# oresat0-plusz-end-card.net
KiCad netlist of a schematic drawn in EAGLE
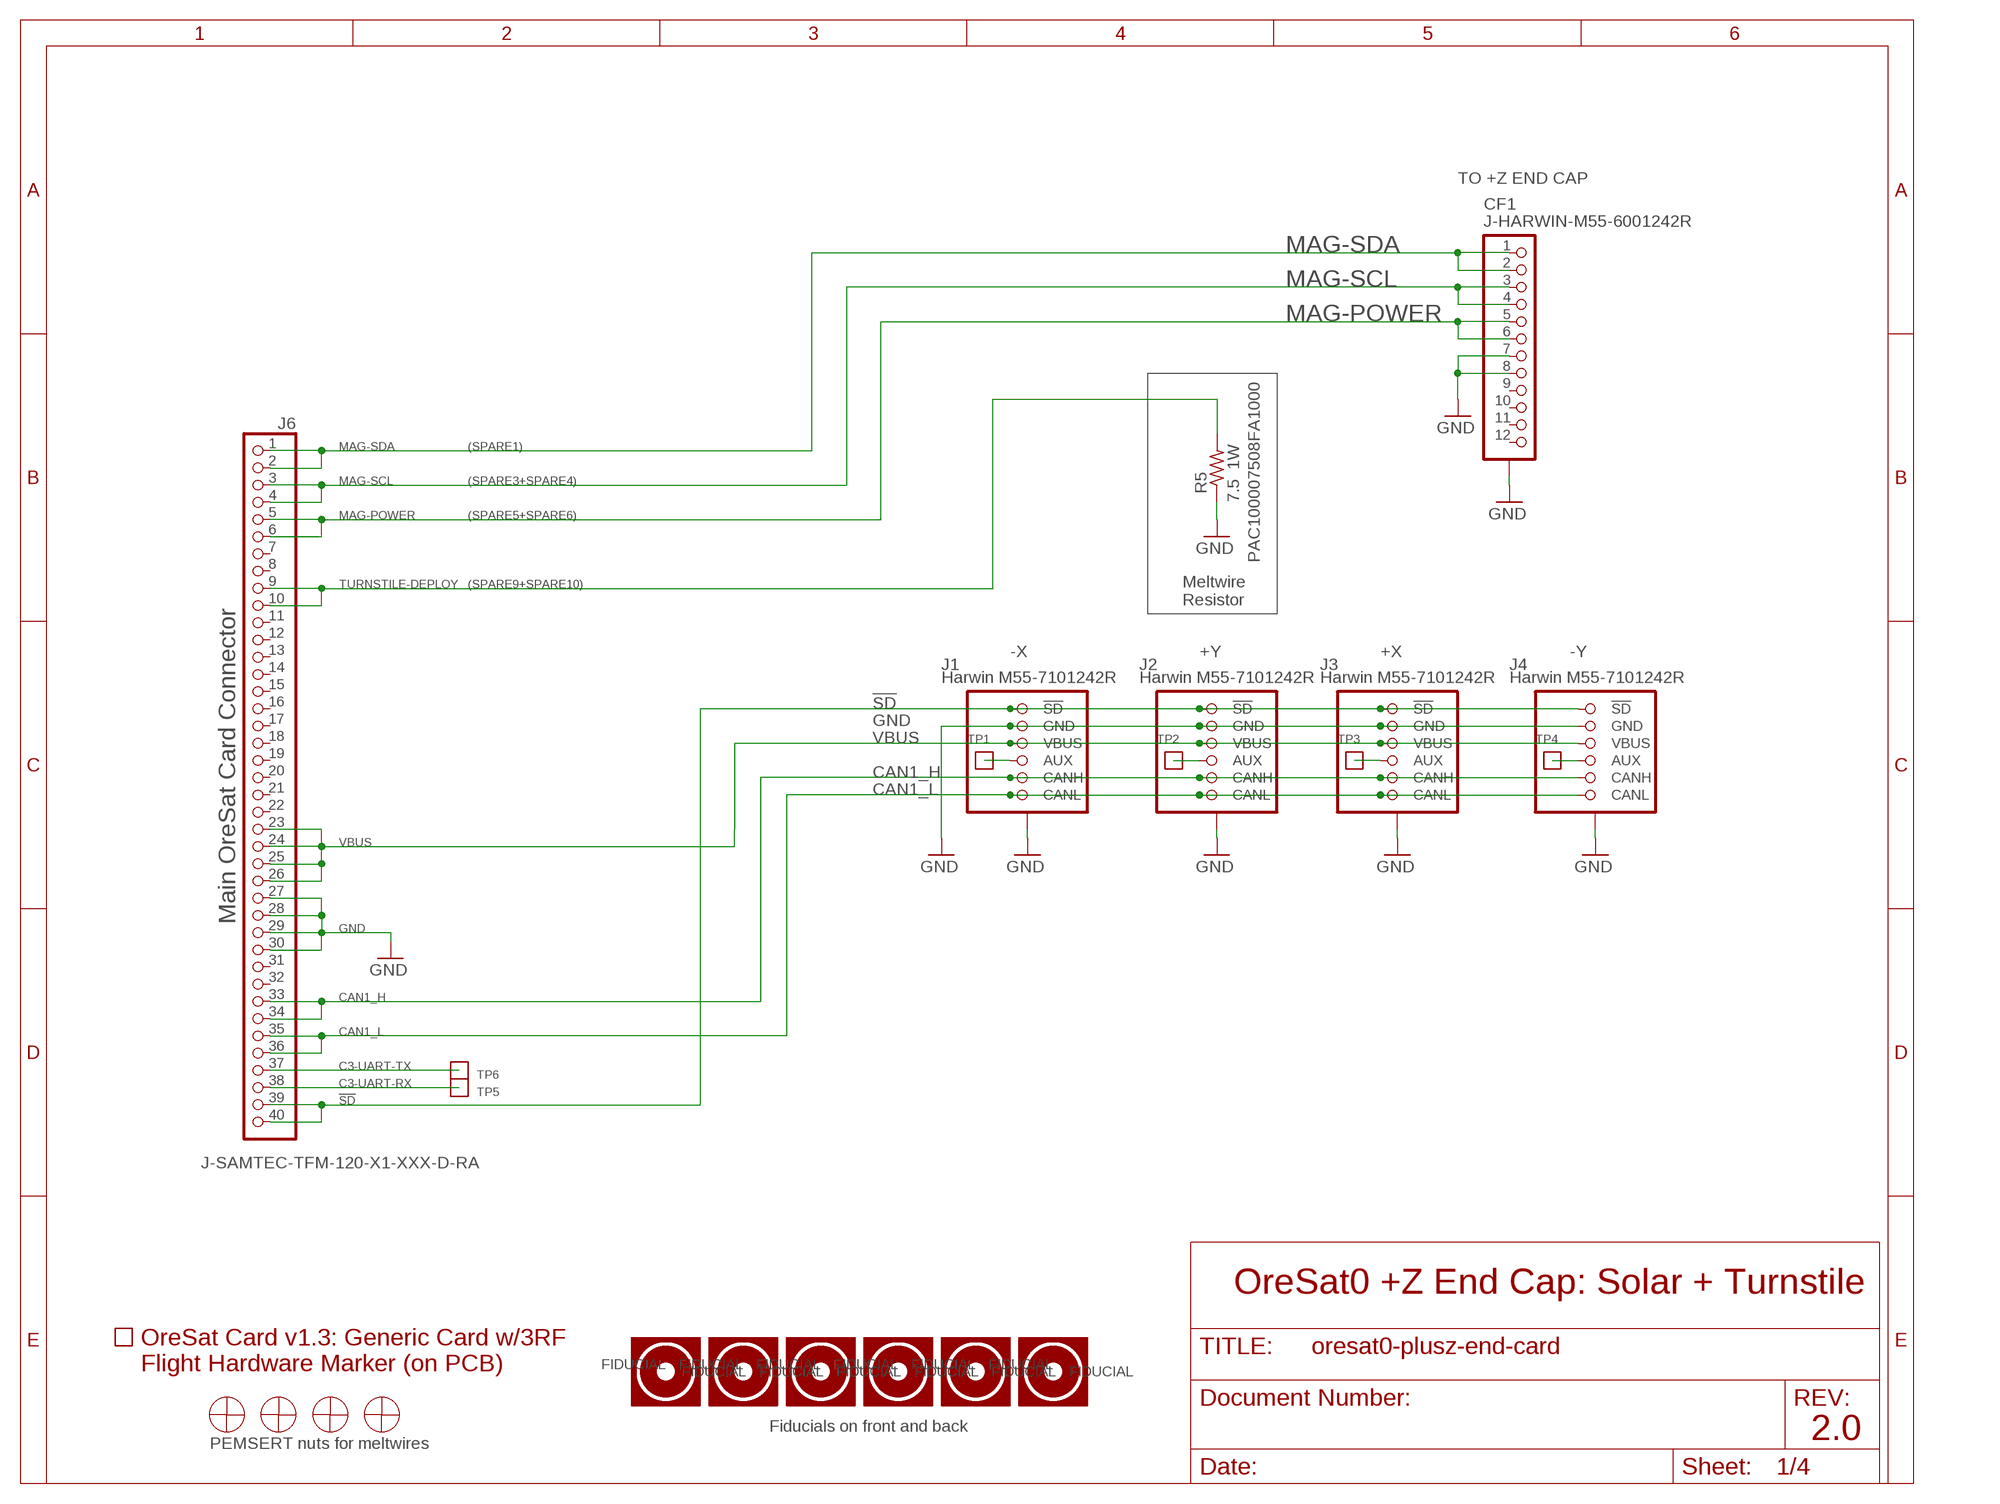
[diagram p0: schematic, sheet 1]
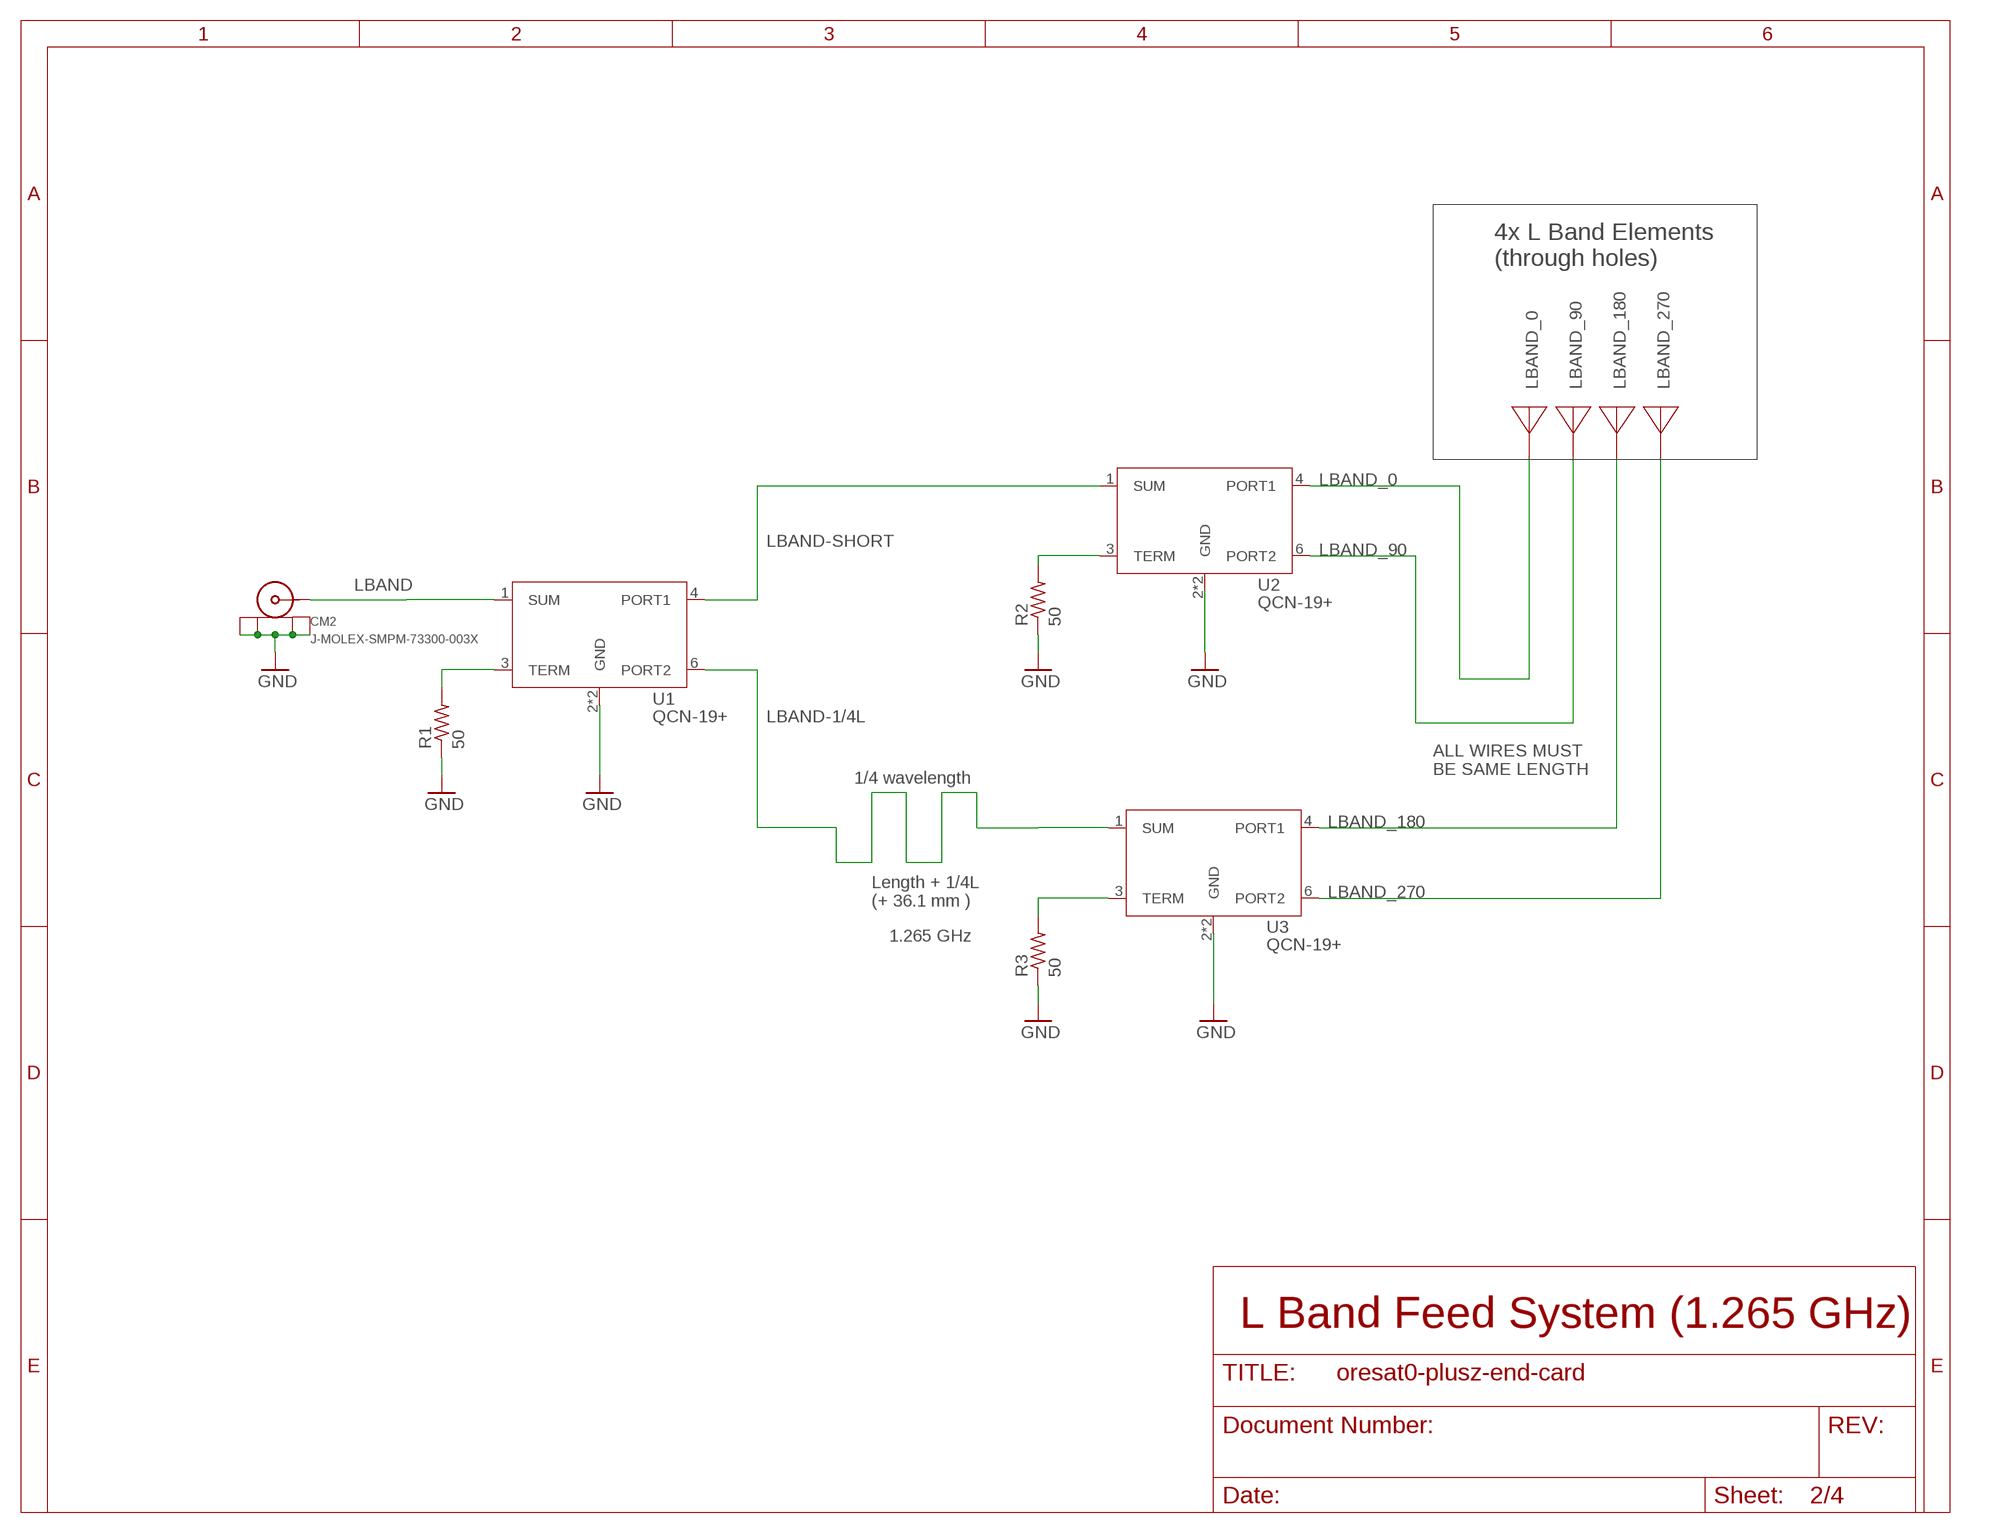
[diagram p1: schematic, sheet 2]
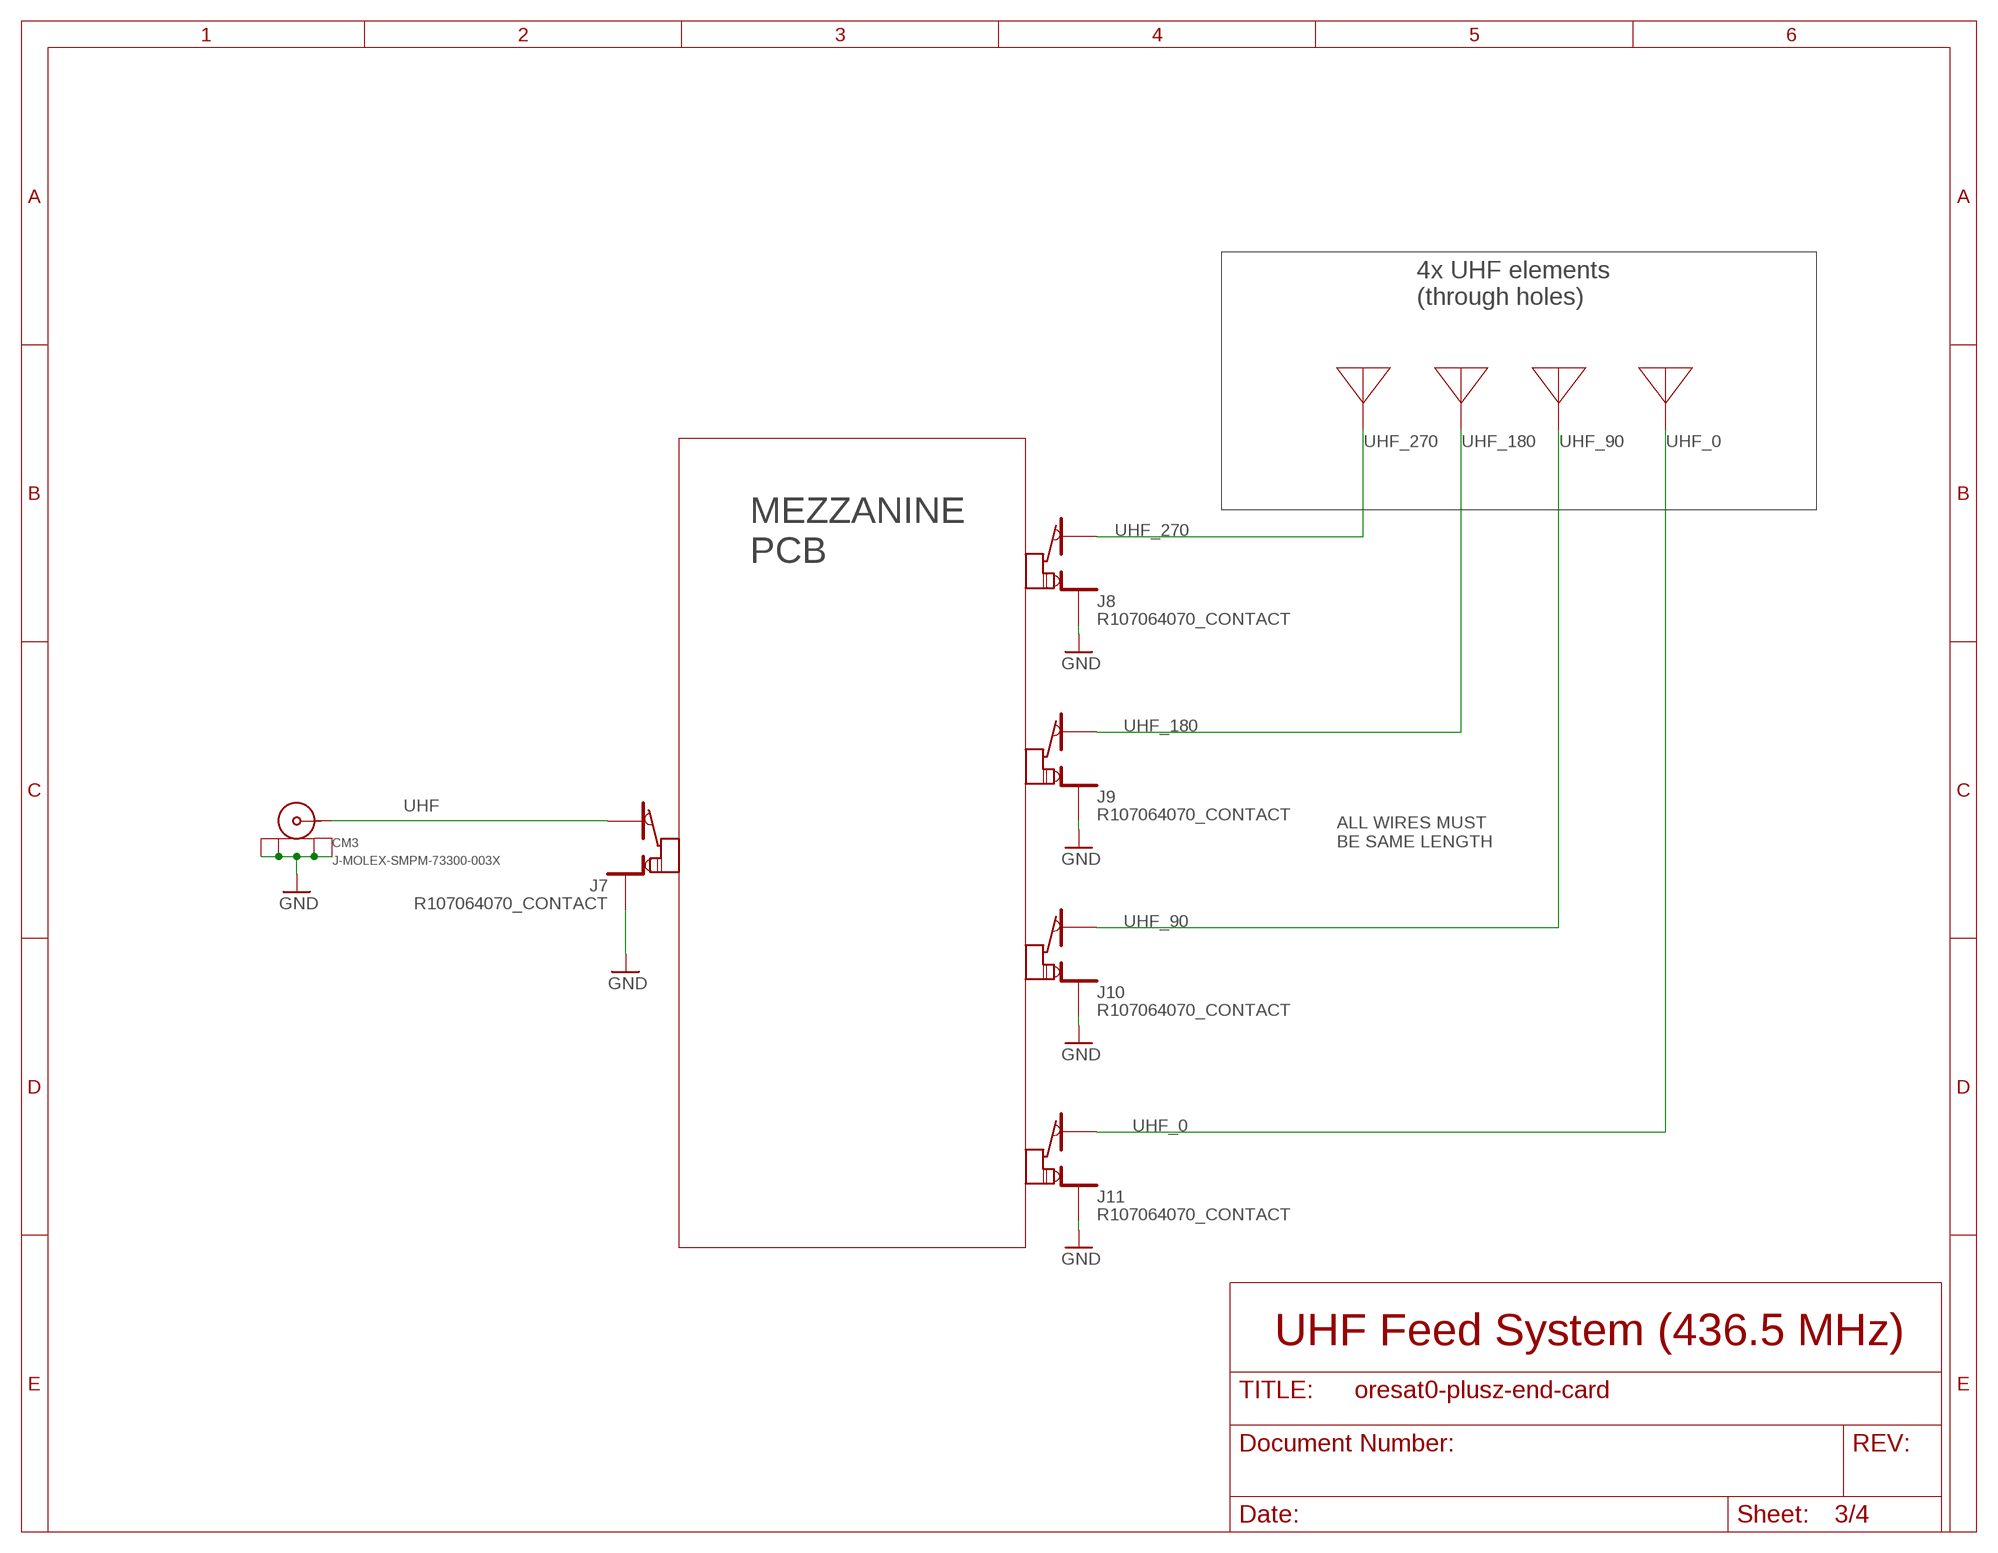
[diagram p2: schematic, sheet 3]
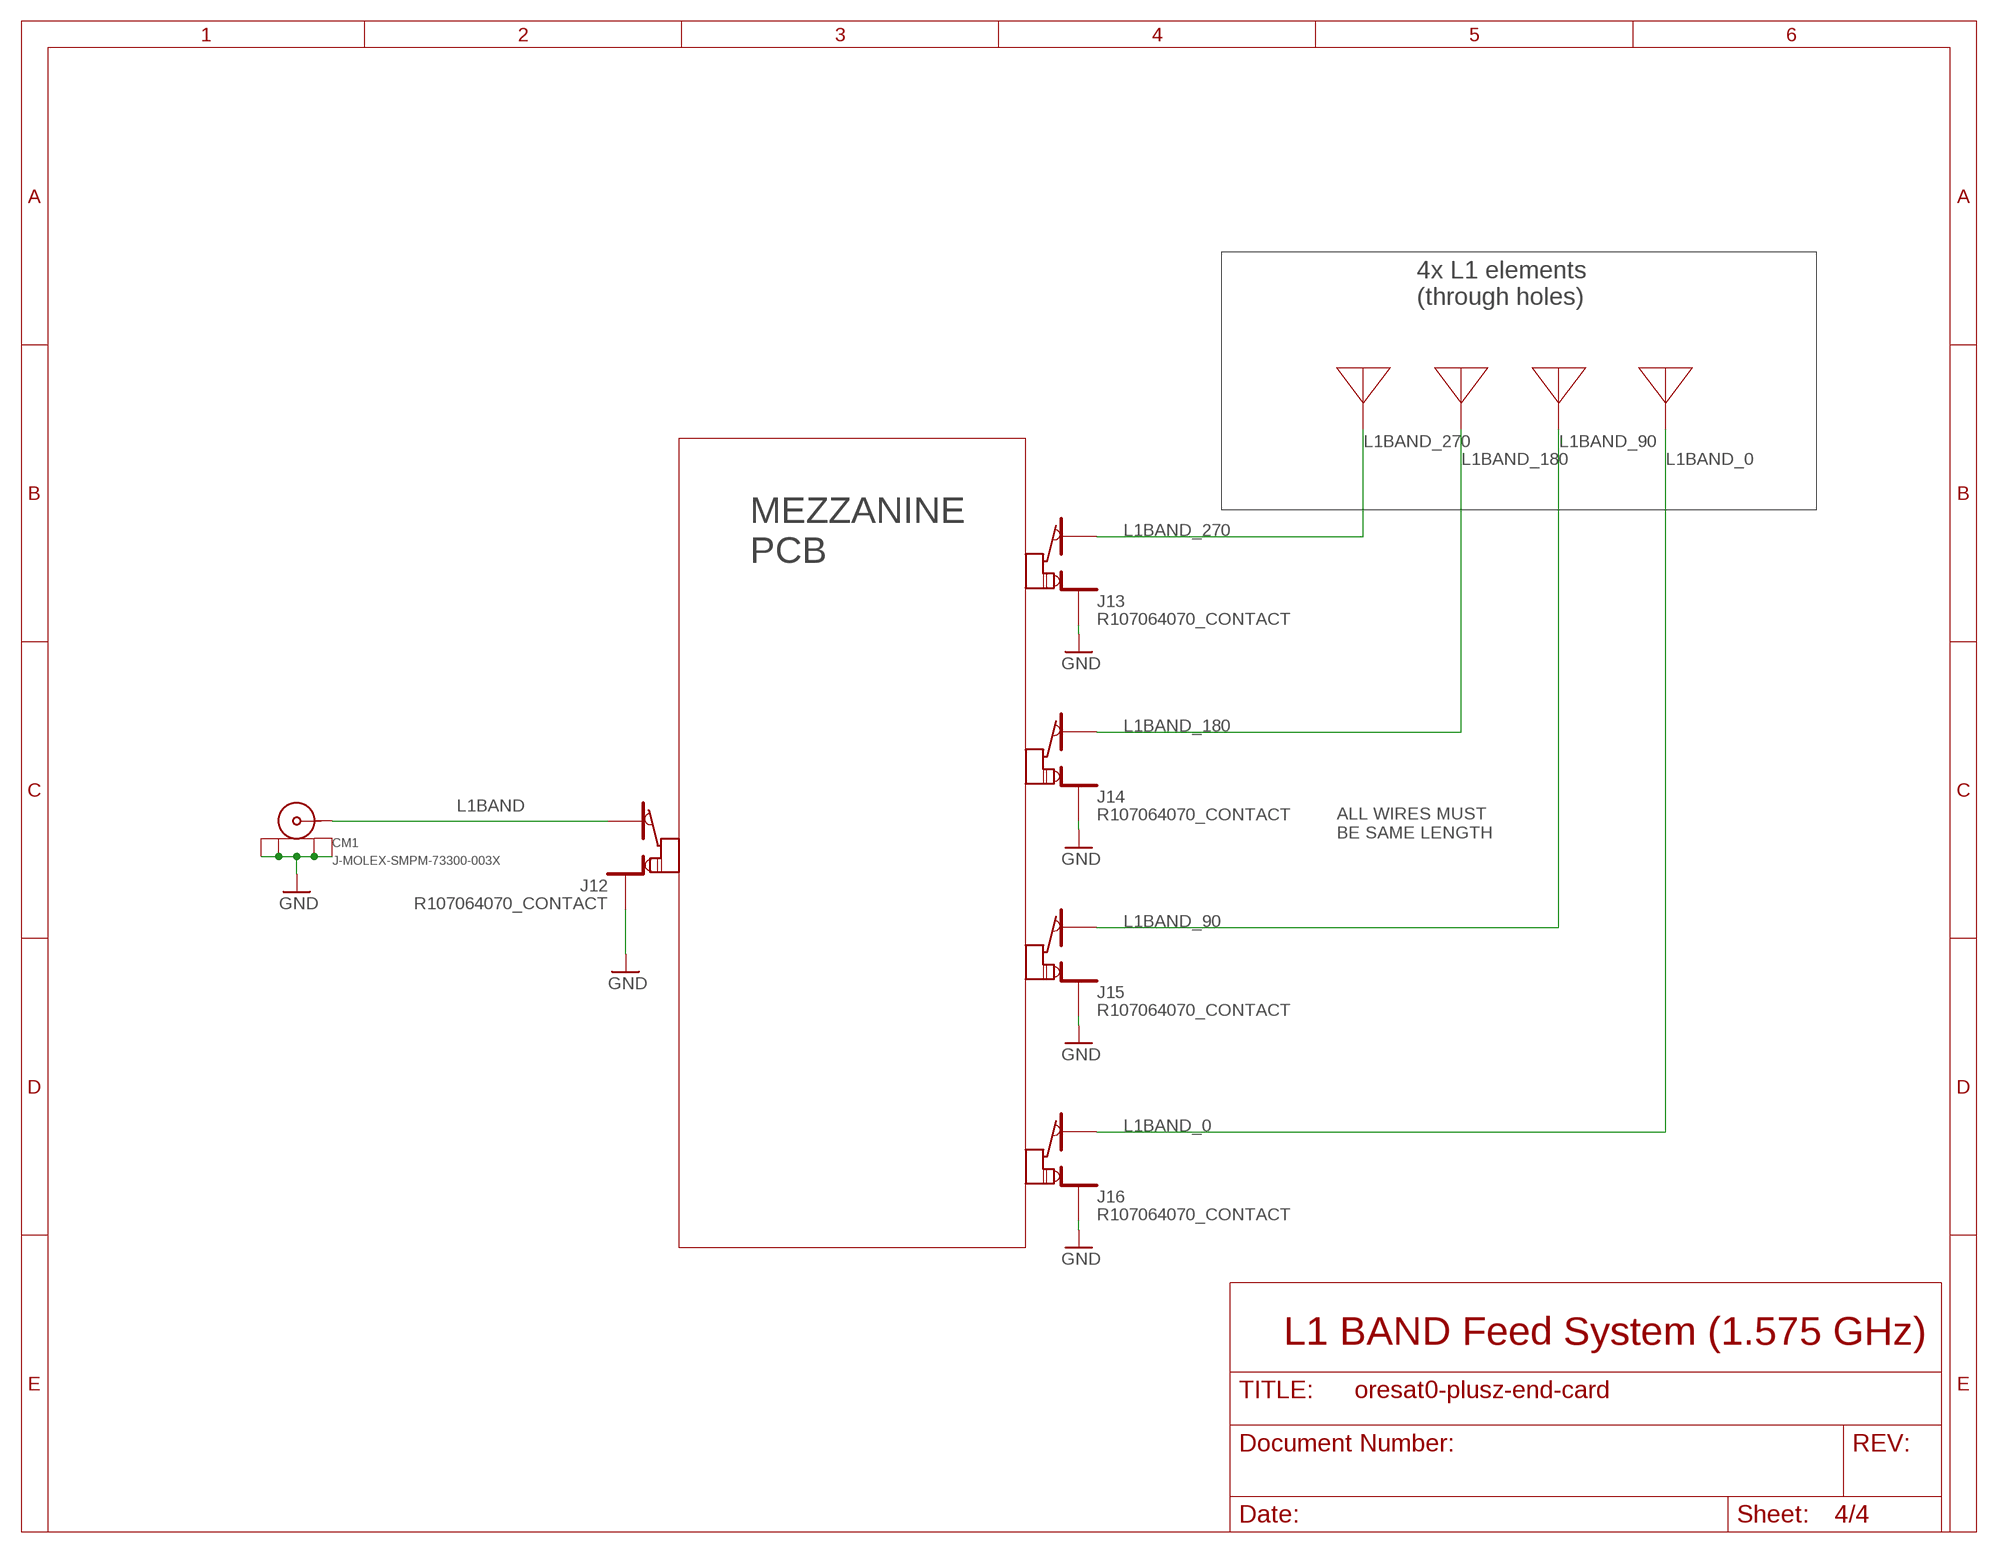
[diagram p3: schematic, sheet 4]

(export (version "E")
  (design (tool "Eeschema 10.0.6"))
  (components
    (comp (ref "CM1")
      (value "J-MOLEX-SMPM-73300-003X")
      (footprint "eagle-import:J-MOLEX-SMPM-073300-003X")
      (fields (field (name "MFG") "MOLEX"))
      (libsource (lib "eagle-import") (part "J-MOLEX-SMPM-73300-003X"))
    )
    (comp (ref "J12")
      (value "R107064070_CONTACT")
      (footprint "eagle-import:R107064070_CONTACT")
      (libsource (lib "eagle-import") (part "R107064070_CONTACT"))
    )
    (comp (ref "J13")
      (value "R107064070_CONTACT")
      (footprint "eagle-import:R107064070_CONTACT")
      (libsource (lib "eagle-import") (part "R107064070_CONTACT"))
    )
    (comp (ref "J14")
      (value "R107064070_CONTACT")
      (footprint "eagle-import:R107064070_CONTACT")
      (libsource (lib "eagle-import") (part "R107064070_CONTACT"))
    )
    (comp (ref "J15")
      (value "R107064070_CONTACT")
      (footprint "eagle-import:R107064070_CONTACT")
      (libsource (lib "eagle-import") (part "R107064070_CONTACT"))
    )
    (comp (ref "J16")
      (value "R107064070_CONTACT")
      (footprint "eagle-import:R107064070_CONTACT")
      (libsource (lib "eagle-import") (part "R107064070_CONTACT"))
    )
    (comp (ref "CM2")
      (value "J-MOLEX-SMPM-73300-003X")
      (footprint "eagle-import:J-MOLEX-SMPM-073300-003X")
      (fields (field (name "MFG") "MOLEX"))
      (libsource (lib "eagle-import") (part "J-MOLEX-SMPM-73300-003X"))
    )
    (comp (ref "R1")
      (value "50")
      (footprint "eagle-import:.0603-C-NOSILK")
      (libsource (lib "eagle-import") (part "R-US_0603-C-NOSILK"))
    )
    (comp (ref "R2")
      (value "50")
      (footprint "eagle-import:.0603-C-NOSILK")
      (libsource (lib "eagle-import") (part "R-US_0603-C-NOSILK"))
    )
    (comp (ref "R3")
      (value "50")
      (footprint "eagle-import:.0603-C-NOSILK")
      (libsource (lib "eagle-import") (part "R-US_0603-C-NOSILK"))
    )
    (comp (ref "U1")
      (value "QCN-19+")
      (footprint "eagle-import:QCN-XXX+")
      (fields (field (name "MFG") "Mini-Circuits"))
      (libsource (lib "eagle-import") (part "QCN-XXX+"))
    )
    (comp (ref "U2")
      (value "QCN-19+")
      (footprint "eagle-import:QCN-XXX+")
      (fields (field (name "MFG") "Mini-Circuits"))
      (libsource (lib "eagle-import") (part "QCN-XXX+"))
    )
    (comp (ref "U3")
      (value "QCN-19+")
      (footprint "eagle-import:QCN-XXX+")
      (fields (field (name "MFG") "Mini-Circuits"))
      (libsource (lib "eagle-import") (part "QCN-XXX+"))
    )
    (comp (ref "CF1")
      (value "J-HARWIN-M55-6001242R")
      (footprint "eagle-import:HARWIN-M55-60X1242R")
      (fields (field (name "MFG") "Harwin"))
      (libsource (lib "eagle-import") (part "J-HARWIN-M55-60X1242R"))
    )
    (comp (ref "FIDUCIAL1")
      (value "FIDUCIAL-1.0X2.0")
      (footprint "eagle-import:FIDUCIAL-1.0X2.0")
      (libsource (lib "eagle-import") (part "FIDUCIAL-1.0X2.0"))
    )
    (comp (ref "FIDUCIAL2")
      (value "FIDUCIAL-1.0X2.0")
      (footprint "eagle-import:FIDUCIAL-1.0X2.0")
      (libsource (lib "eagle-import") (part "FIDUCIAL-1.0X2.0"))
    )
    (comp (ref "FIDUCIAL3")
      (value "FIDUCIAL-1.0X2.0")
      (footprint "eagle-import:FIDUCIAL-1.0X2.0")
      (libsource (lib "eagle-import") (part "FIDUCIAL-1.0X2.0"))
    )
    (comp (ref "FIDUCIAL4")
      (value "FIDUCIAL-1.0X2.0")
      (footprint "eagle-import:FIDUCIAL-1.0X2.0")
      (libsource (lib "eagle-import") (part "FIDUCIAL-1.0X2.0"))
    )
    (comp (ref "FIDUCIAL5")
      (value "FIDUCIAL-1.0X2.0")
      (footprint "eagle-import:FIDUCIAL-1.0X2.0")
      (libsource (lib "eagle-import") (part "FIDUCIAL-1.0X2.0"))
    )
    (comp (ref "FIDUCIAL6")
      (value "FIDUCIAL-1.0X2.0")
      (footprint "eagle-import:FIDUCIAL-1.0X2.0")
      (libsource (lib "eagle-import") (part "FIDUCIAL-1.0X2.0"))
    )
    (comp (ref "HW1")
      (value "MCMASTER-94100A150")
      (footprint "eagle-import:MCMASTER-94100A150")
      (libsource (lib "eagle-import") (part "MCMASTER-94100A150"))
    )
    (comp (ref "HW2")
      (value "MCMASTER-94100A150")
      (footprint "eagle-import:MCMASTER-94100A150")
      (libsource (lib "eagle-import") (part "MCMASTER-94100A150"))
    )
    (comp (ref "HW3")
      (value "MCMASTER-94100A150")
      (footprint "eagle-import:MCMASTER-94100A150")
      (libsource (lib "eagle-import") (part "MCMASTER-94100A150"))
    )
    (comp (ref "HW4")
      (value "MCMASTER-94100A150")
      (footprint "eagle-import:MCMASTER-94100A150")
      (libsource (lib "eagle-import") (part "MCMASTER-94100A150"))
    )
    (comp (ref "J1")
      (value "Harwin M55-7101242R")
      (footprint "eagle-import:M55-7101242R")
      (fields (field (name "MFG") "Harwin Inc."))
      (libsource (lib "eagle-import") (part "SOLAR-CARD-CONNECTOR"))
    )
    (comp (ref "J2")
      (value "Harwin M55-7101242R")
      (footprint "eagle-import:M55-7101242R")
      (fields (field (name "MFG") "Harwin Inc."))
      (libsource (lib "eagle-import") (part "SOLAR-CARD-CONNECTOR"))
    )
    (comp (ref "J3")
      (value "Harwin M55-7101242R")
      (footprint "eagle-import:M55-7101242R")
      (fields (field (name "MFG") "Harwin Inc."))
      (libsource (lib "eagle-import") (part "SOLAR-CARD-CONNECTOR"))
    )
    (comp (ref "J4")
      (value "Harwin M55-7101242R")
      (footprint "eagle-import:M55-7101242R")
      (fields (field (name "MFG") "Harwin Inc."))
      (libsource (lib "eagle-import") (part "SOLAR-CARD-CONNECTOR"))
    )
    (comp (ref "J6")
      (value "J-SAMTEC-TFM-120-X1-XXX-D-RA")
      (footprint "eagle-import:J-SAMTEC-TFM-120-X1-XXX-D-RA")
      (fields (field (name "MFR") "Samtec") (field (name "MPN") "TFM-120-01-L-D-RA"))
      (libsource (lib "eagle-import") (part "J-SAMTEC-TFM-120-X1-XXX-D-RA"))
    )
    (comp (ref "PCB1")
      (value "ORESAT-CARD-V1.3-GENERIC-3RF")
      (footprint "eagle-import:ORESAT-CARD-V1.3-GENERIC-3RF")
      (libsource (lib "eagle-import") (part "ORESAT-CARD-V1.3-GENERIC-3RF"))
    )
    (comp (ref "R5")
      (value "7.5 1W")
      (footprint "eagle-import:PAC100-FOR-MELTWIRE")
      (libsource (lib "eagle-import") (part "PAC100-FOR-MELTWIRE"))
    )
    (comp (ref "TP1")
      (value "TEST-POINT-LARGE-SQUARE")
      (footprint "eagle-import:1X01")
      (libsource (lib "eagle-import") (part "TEST-POINT-LARGE-SQUARE"))
    )
    (comp (ref "TP2")
      (value "TEST-POINT-LARGE-SQUARE")
      (footprint "eagle-import:1X01")
      (libsource (lib "eagle-import") (part "TEST-POINT-LARGE-SQUARE"))
    )
    (comp (ref "TP3")
      (value "TEST-POINT-LARGE-SQUARE")
      (footprint "eagle-import:1X01")
      (libsource (lib "eagle-import") (part "TEST-POINT-LARGE-SQUARE"))
    )
    (comp (ref "TP4")
      (value "TEST-POINT-LARGE-SQUARE")
      (footprint "eagle-import:1X01")
      (libsource (lib "eagle-import") (part "TEST-POINT-LARGE-SQUARE"))
    )
    (comp (ref "TP5")
      (value "TEST-POINT-LARGE-SQUARE")
      (footprint "eagle-import:1X01")
      (libsource (lib "eagle-import") (part "TEST-POINT-LARGE-SQUARE"))
    )
    (comp (ref "TP6")
      (value "TEST-POINT-LARGE-SQUARE")
      (footprint "eagle-import:1X01")
      (libsource (lib "eagle-import") (part "TEST-POINT-LARGE-SQUARE"))
    )
    (comp (ref "U$1")
      (value "FLIGHMARKERNEW")
      (footprint "eagle-import:FLIGHTMARKER_NEW_BOARDS")
      (libsource (lib "eagle-import") (part "FLIGHMARKERNEW"))
    )
    (comp (ref "CM3")
      (value "J-MOLEX-SMPM-73300-003X")
      (footprint "eagle-import:J-MOLEX-SMPM-073300-003X")
      (fields (field (name "MFG") "MOLEX"))
      (libsource (lib "eagle-import") (part "J-MOLEX-SMPM-73300-003X"))
    )
    (comp (ref "J7")
      (value "R107064070_CONTACT")
      (footprint "eagle-import:R107064070_CONTACT")
      (libsource (lib "eagle-import") (part "R107064070_CONTACT"))
    )
    (comp (ref "J8")
      (value "R107064070_CONTACT")
      (footprint "eagle-import:R107064070_CONTACT")
      (libsource (lib "eagle-import") (part "R107064070_CONTACT"))
    )
    (comp (ref "J9")
      (value "R107064070_CONTACT")
      (footprint "eagle-import:R107064070_CONTACT")
      (libsource (lib "eagle-import") (part "R107064070_CONTACT"))
    )
    (comp (ref "J10")
      (value "R107064070_CONTACT")
      (footprint "eagle-import:R107064070_CONTACT")
      (libsource (lib "eagle-import") (part "R107064070_CONTACT"))
    )
    (comp (ref "J11")
      (value "R107064070_CONTACT")
      (footprint "eagle-import:R107064070_CONTACT")
      (libsource (lib "eagle-import") (part "R107064070_CONTACT"))
    )
  )
  (nets
    (net (code "1") (name "C3-UART-RX") (class "Default")
      (node (ref "J6") (pin "38") (pinfunction "38_38") (pintype "passive"))
      (node (ref "TP5") (pin "1") (pinfunction "1_1") (pintype "passive"))
    )
    (net (code "2") (name "C3-UART-TX") (class "Default")
      (node (ref "J6") (pin "37") (pinfunction "37_37") (pintype "passive"))
      (node (ref "TP6") (pin "1") (pinfunction "1_1") (pintype "passive"))
    )
    (net (code "3") (name "CAN1_H") (class "Default")
      (node (ref "J1") (pin "10") (pinfunction "CANH_10") (pintype "passive"))
      (node (ref "J1") (pin "9") (pinfunction "CANH_9") (pintype "passive"))
      (node (ref "J2") (pin "10") (pinfunction "CANH_10") (pintype "passive"))
      (node (ref "J2") (pin "9") (pinfunction "CANH_9") (pintype "passive"))
      (node (ref "J3") (pin "10") (pinfunction "CANH_10") (pintype "passive"))
      (node (ref "J3") (pin "9") (pinfunction "CANH_9") (pintype "passive"))
      (node (ref "J4") (pin "10") (pinfunction "CANH_10") (pintype "passive"))
      (node (ref "J4") (pin "9") (pinfunction "CANH_9") (pintype "passive"))
      (node (ref "J6") (pin "33") (pinfunction "33_33") (pintype "passive"))
      (node (ref "J6") (pin "34") (pinfunction "34_34") (pintype "passive"))
    )
    (net (code "4") (name "CAN1_L") (class "Default")
      (node (ref "J1") (pin "11") (pinfunction "CANL_11") (pintype "passive"))
      (node (ref "J1") (pin "12") (pinfunction "CANL_12") (pintype "passive"))
      (node (ref "J2") (pin "11") (pinfunction "CANL_11") (pintype "passive"))
      (node (ref "J2") (pin "12") (pinfunction "CANL_12") (pintype "passive"))
      (node (ref "J3") (pin "11") (pinfunction "CANL_11") (pintype "passive"))
      (node (ref "J3") (pin "12") (pinfunction "CANL_12") (pintype "passive"))
      (node (ref "J4") (pin "11") (pinfunction "CANL_11") (pintype "passive"))
      (node (ref "J4") (pin "12") (pinfunction "CANL_12") (pintype "passive"))
      (node (ref "J6") (pin "35") (pinfunction "35_35") (pintype "passive"))
      (node (ref "J6") (pin "36") (pinfunction "36_36") (pintype "passive"))
    )
    (net (code "5") (name "GND") (class "Default")
      (node (ref "CF1") (pin "7") (pinfunction "7_7") (pintype "passive"))
      (node (ref "CF1") (pin "8") (pinfunction "8_8") (pintype "passive"))
      (node (ref "CF1") (pin "P$1") (pinfunction "SHIELDS_P$1") (pintype "passive"))
      (node (ref "CF1") (pin "P$2") (pinfunction "SHIELDS_P$2") (pintype "passive"))
      (node (ref "CF1") (pin "P$3") (pinfunction "SHIELDS_P$3") (pintype "passive"))
      (node (ref "CF1") (pin "P$4") (pinfunction "SHIELDS_P$4") (pintype "passive"))
      (node (ref "CM1") (pin "P$1") (pinfunction "SHIELD3_P$1") (pintype "passive"))
      (node (ref "CM1") (pin "P$2") (pinfunction "SHIELD2_P$2") (pintype "passive"))
      (node (ref "CM1") (pin "P$3") (pinfunction "SHIELD1_P$3") (pintype "passive"))
      (node (ref "CM1") (pin "P$4") (pinfunction "SHIELD_P$4") (pintype "passive"))
      (node (ref "CM2") (pin "P$1") (pinfunction "SHIELD3_P$1") (pintype "passive"))
      (node (ref "CM2") (pin "P$2") (pinfunction "SHIELD2_P$2") (pintype "passive"))
      (node (ref "CM2") (pin "P$3") (pinfunction "SHIELD1_P$3") (pintype "passive"))
      (node (ref "CM2") (pin "P$4") (pinfunction "SHIELD_P$4") (pintype "passive"))
      (node (ref "CM3") (pin "P$1") (pinfunction "SHIELD3_P$1") (pintype "passive"))
      (node (ref "CM3") (pin "P$2") (pinfunction "SHIELD2_P$2") (pintype "passive"))
      (node (ref "CM3") (pin "P$3") (pinfunction "SHIELD1_P$3") (pintype "passive"))
      (node (ref "CM3") (pin "P$4") (pinfunction "SHIELD_P$4") (pintype "passive"))
      (node (ref "J1") (pin "3") (pinfunction "GND_3") (pintype "passive"))
      (node (ref "J1") (pin "4") (pinfunction "GND_4") (pintype "passive"))
      (node (ref "J1") (pin "P$1") (pinfunction "SHIELD_P$1") (pintype "passive"))
      (node (ref "J1") (pin "P$2") (pinfunction "SHIELD_P$2") (pintype "passive"))
      (node (ref "J1") (pin "P$3") (pinfunction "SHIELD_P$3") (pintype "passive"))
      (node (ref "J1") (pin "P$4") (pinfunction "SHIELD_P$4") (pintype "passive"))
      (node (ref "J10") (pin "P$2") (pinfunction "P$2_P$2") (pintype "bidirectional"))
      (node (ref "J10") (pin "P$3") (pinfunction "P$2_P$3") (pintype "bidirectional"))
      (node (ref "J11") (pin "P$2") (pinfunction "P$2_P$2") (pintype "bidirectional"))
      (node (ref "J11") (pin "P$3") (pinfunction "P$2_P$3") (pintype "bidirectional"))
      (node (ref "J12") (pin "P$2") (pinfunction "P$2_P$2") (pintype "bidirectional"))
      (node (ref "J12") (pin "P$3") (pinfunction "P$2_P$3") (pintype "bidirectional"))
      (node (ref "J13") (pin "P$2") (pinfunction "P$2_P$2") (pintype "bidirectional"))
      (node (ref "J13") (pin "P$3") (pinfunction "P$2_P$3") (pintype "bidirectional"))
      (node (ref "J14") (pin "P$2") (pinfunction "P$2_P$2") (pintype "bidirectional"))
      (node (ref "J14") (pin "P$3") (pinfunction "P$2_P$3") (pintype "bidirectional"))
      (node (ref "J15") (pin "P$2") (pinfunction "P$2_P$2") (pintype "bidirectional"))
      (node (ref "J15") (pin "P$3") (pinfunction "P$2_P$3") (pintype "bidirectional"))
      (node (ref "J16") (pin "P$2") (pinfunction "P$2_P$2") (pintype "bidirectional"))
      (node (ref "J16") (pin "P$3") (pinfunction "P$2_P$3") (pintype "bidirectional"))
      (node (ref "J2") (pin "3") (pinfunction "GND_3") (pintype "passive"))
      (node (ref "J2") (pin "4") (pinfunction "GND_4") (pintype "passive"))
      (node (ref "J2") (pin "P$1") (pinfunction "SHIELD_P$1") (pintype "passive"))
      (node (ref "J2") (pin "P$2") (pinfunction "SHIELD_P$2") (pintype "passive"))
      (node (ref "J2") (pin "P$3") (pinfunction "SHIELD_P$3") (pintype "passive"))
      (node (ref "J2") (pin "P$4") (pinfunction "SHIELD_P$4") (pintype "passive"))
      (node (ref "J3") (pin "3") (pinfunction "GND_3") (pintype "passive"))
      (node (ref "J3") (pin "4") (pinfunction "GND_4") (pintype "passive"))
      (node (ref "J3") (pin "P$1") (pinfunction "SHIELD_P$1") (pintype "passive"))
      (node (ref "J3") (pin "P$2") (pinfunction "SHIELD_P$2") (pintype "passive"))
      (node (ref "J3") (pin "P$3") (pinfunction "SHIELD_P$3") (pintype "passive"))
      (node (ref "J3") (pin "P$4") (pinfunction "SHIELD_P$4") (pintype "passive"))
      (node (ref "J4") (pin "3") (pinfunction "GND_3") (pintype "passive"))
      (node (ref "J4") (pin "4") (pinfunction "GND_4") (pintype "passive"))
      (node (ref "J4") (pin "P$1") (pinfunction "SHIELD_P$1") (pintype "passive"))
      (node (ref "J4") (pin "P$2") (pinfunction "SHIELD_P$2") (pintype "passive"))
      (node (ref "J4") (pin "P$3") (pinfunction "SHIELD_P$3") (pintype "passive"))
      (node (ref "J4") (pin "P$4") (pinfunction "SHIELD_P$4") (pintype "passive"))
      (node (ref "J6") (pin "27") (pinfunction "27_27") (pintype "passive"))
      (node (ref "J6") (pin "28") (pinfunction "28_28") (pintype "passive"))
      (node (ref "J6") (pin "29") (pinfunction "29_29") (pintype "passive"))
      (node (ref "J6") (pin "30") (pinfunction "30_30") (pintype "passive"))
      (node (ref "J7") (pin "P$2") (pinfunction "P$2_P$2") (pintype "bidirectional"))
      (node (ref "J7") (pin "P$3") (pinfunction "P$2_P$3") (pintype "bidirectional"))
      (node (ref "J8") (pin "P$2") (pinfunction "P$2_P$2") (pintype "bidirectional"))
      (node (ref "J8") (pin "P$3") (pinfunction "P$2_P$3") (pintype "bidirectional"))
      (node (ref "J9") (pin "P$2") (pinfunction "P$2_P$2") (pintype "bidirectional"))
      (node (ref "J9") (pin "P$3") (pinfunction "P$2_P$3") (pintype "bidirectional"))
      (node (ref "R1") (pin "1") (pinfunction "1_1") (pintype "passive"))
      (node (ref "R2") (pin "1") (pinfunction "1_1") (pintype "passive"))
      (node (ref "R3") (pin "1") (pinfunction "1_1") (pintype "passive"))
      (node (ref "R5") (pin "P$1") (pinfunction "1_P$1") (pintype "passive"))
      (node (ref "R5") (pin "P$2") (pinfunction "1_P$2") (pintype "passive"))
      (node (ref "U1") (pin "2") (pinfunction "GND_2") (pintype "power_in"))
      (node (ref "U1") (pin "5") (pinfunction "GND_5") (pintype "power_in"))
      (node (ref "U2") (pin "2") (pinfunction "GND_2") (pintype "power_in"))
      (node (ref "U2") (pin "5") (pinfunction "GND_5") (pintype "power_in"))
      (node (ref "U3") (pin "2") (pinfunction "GND_2") (pintype "power_in"))
      (node (ref "U3") (pin "5") (pinfunction "GND_5") (pintype "power_in"))
    )
    (net (code "6") (name "L1BAND") (class "Default")
      (node (ref "CM1") (pin "RF") (pinfunction "CENTER_RF") (pintype "passive"))
      (node (ref "J12") (pin "P$1") (pinfunction "P$1_P$1") (pintype "bidirectional"))
    )
    (net (code "7") (name "L1BAND_0") (class "Default")
      (node (ref "J16") (pin "P$1") (pinfunction "P$1_P$1") (pintype "bidirectional"))
    )
    (net (code "8") (name "L1BAND_90") (class "Default")
      (node (ref "J15") (pin "P$1") (pinfunction "P$1_P$1") (pintype "bidirectional"))
    )
    (net (code "9") (name "L1BAND_180") (class "Default")
      (node (ref "J14") (pin "P$1") (pinfunction "P$1_P$1") (pintype "bidirectional"))
    )
    (net (code "10") (name "L1BAND_270") (class "Default")
      (node (ref "J13") (pin "P$1") (pinfunction "P$1_P$1") (pintype "bidirectional"))
    )
    (net (code "11") (name "LBAND") (class "Default")
      (node (ref "CM2") (pin "RF") (pinfunction "CENTER_RF") (pintype "passive"))
      (node (ref "U1") (pin "1") (pinfunction "SUM_1") (pintype "bidirectional"))
    )
    (net (code "12") (name "LBAND-1{slash}4L") (class "Default")
      (node (ref "U1") (pin "6") (pinfunction "PORT2_6") (pintype "bidirectional"))
      (node (ref "U3") (pin "1") (pinfunction "SUM_1") (pintype "bidirectional"))
    )
    (net (code "13") (name "LBAND-SHORT") (class "Default")
      (node (ref "U1") (pin "4") (pinfunction "PORT1_4") (pintype "bidirectional"))
      (node (ref "U2") (pin "1") (pinfunction "SUM_1") (pintype "bidirectional"))
    )
    (net (code "14") (name "LBAND_0") (class "Default")
      (node (ref "U2") (pin "4") (pinfunction "PORT1_4") (pintype "bidirectional"))
    )
    (net (code "15") (name "LBAND_90") (class "Default")
      (node (ref "U2") (pin "6") (pinfunction "PORT2_6") (pintype "bidirectional"))
    )
    (net (code "16") (name "LBAND_180") (class "Default")
      (node (ref "U3") (pin "4") (pinfunction "PORT1_4") (pintype "bidirectional"))
    )
    (net (code "17") (name "LBAND_270") (class "Default")
      (node (ref "U3") (pin "6") (pinfunction "PORT2_6") (pintype "bidirectional"))
    )
    (net (code "18") (name "MAG-POWER") (class "Default")
      (node (ref "CF1") (pin "5") (pinfunction "5_5") (pintype "passive"))
      (node (ref "CF1") (pin "6") (pinfunction "6_6") (pintype "passive"))
      (node (ref "J6") (pin "5") (pinfunction "5_5") (pintype "passive"))
      (node (ref "J6") (pin "6") (pinfunction "6_6") (pintype "passive"))
    )
    (net (code "19") (name "MAG-SCL") (class "Default")
      (node (ref "CF1") (pin "3") (pinfunction "3_3") (pintype "passive"))
      (node (ref "CF1") (pin "4") (pinfunction "4_4") (pintype "passive"))
      (node (ref "J6") (pin "3") (pinfunction "3_3") (pintype "passive"))
      (node (ref "J6") (pin "4") (pinfunction "4_4") (pintype "passive"))
    )
    (net (code "20") (name "MAG-SDA") (class "Default")
      (node (ref "CF1") (pin "1") (pinfunction "1_1") (pintype "passive"))
      (node (ref "CF1") (pin "2") (pinfunction "2_2") (pintype "passive"))
      (node (ref "J6") (pin "1") (pinfunction "1_1") (pintype "passive"))
      (node (ref "J6") (pin "2") (pinfunction "2_2") (pintype "passive"))
    )
    (net (code "21") (name "Net-(J1-AUX-Pad7)") (class "Default")
      (node (ref "J1") (pin "7") (pinfunction "AUX_7") (pintype "passive"))
      (node (ref "J1") (pin "8") (pinfunction "AUX_8") (pintype "passive"))
      (node (ref "TP1") (pin "1") (pinfunction "1_1") (pintype "passive"))
    )
    (net (code "22") (name "Net-(J2-AUX-Pad7)") (class "Default")
      (node (ref "J2") (pin "7") (pinfunction "AUX_7") (pintype "passive"))
      (node (ref "J2") (pin "8") (pinfunction "AUX_8") (pintype "passive"))
      (node (ref "TP2") (pin "1") (pinfunction "1_1") (pintype "passive"))
    )
    (net (code "23") (name "Net-(J3-AUX-Pad7)") (class "Default")
      (node (ref "J3") (pin "7") (pinfunction "AUX_7") (pintype "passive"))
      (node (ref "J3") (pin "8") (pinfunction "AUX_8") (pintype "passive"))
      (node (ref "TP3") (pin "1") (pinfunction "1_1") (pintype "passive"))
    )
    (net (code "24") (name "Net-(J4-AUX-Pad7)") (class "Default")
      (node (ref "J4") (pin "7") (pinfunction "AUX_7") (pintype "passive"))
      (node (ref "J4") (pin "8") (pinfunction "AUX_8") (pintype "passive"))
      (node (ref "TP4") (pin "1") (pinfunction "1_1") (pintype "passive"))
    )
    (net (code "25") (name "Net-(U1-TERM)") (class "Default")
      (node (ref "R1") (pin "2") (pinfunction "2_2") (pintype "passive"))
      (node (ref "U1") (pin "3") (pinfunction "TERM_3") (pintype "bidirectional"))
    )
    (net (code "26") (name "Net-(U2-TERM)") (class "Default")
      (node (ref "R2") (pin "2") (pinfunction "2_2") (pintype "passive"))
      (node (ref "U2") (pin "3") (pinfunction "TERM_3") (pintype "bidirectional"))
    )
    (net (code "27") (name "Net-(U3-TERM)") (class "Default")
      (node (ref "R3") (pin "2") (pinfunction "2_2") (pintype "passive"))
      (node (ref "U3") (pin "3") (pinfunction "TERM_3") (pintype "bidirectional"))
    )
    (net (code "28") (name "TURNSTILE-DEPLOY") (class "Default")
      (node (ref "J6") (pin "10") (pinfunction "10_10") (pintype "passive"))
      (node (ref "J6") (pin "9") (pinfunction "9_9") (pintype "passive"))
      (node (ref "R5") (pin "P$3") (pinfunction "2_P$3") (pintype "passive"))
      (node (ref "R5") (pin "P$4") (pinfunction "2_P$4") (pintype "passive"))
    )
    (net (code "29") (name "UHF") (class "Default")
      (node (ref "CM3") (pin "RF") (pinfunction "CENTER_RF") (pintype "passive"))
      (node (ref "J7") (pin "P$1") (pinfunction "P$1_P$1") (pintype "bidirectional"))
    )
    (net (code "30") (name "UHF_0") (class "Default")
      (node (ref "J11") (pin "P$1") (pinfunction "P$1_P$1") (pintype "bidirectional"))
    )
    (net (code "31") (name "UHF_90") (class "Default")
      (node (ref "J10") (pin "P$1") (pinfunction "P$1_P$1") (pintype "bidirectional"))
    )
    (net (code "32") (name "UHF_180") (class "Default")
      (node (ref "J9") (pin "P$1") (pinfunction "P$1_P$1") (pintype "bidirectional"))
    )
    (net (code "33") (name "UHF_270") (class "Default")
      (node (ref "J8") (pin "P$1") (pinfunction "P$1_P$1") (pintype "bidirectional"))
    )
    (net (code "34") (name "VBUS") (class "Default")
      (node (ref "J1") (pin "5") (pinfunction "VBUS_5") (pintype "passive"))
      (node (ref "J1") (pin "6") (pinfunction "VBUS_6") (pintype "passive"))
      (node (ref "J2") (pin "5") (pinfunction "VBUS_5") (pintype "passive"))
      (node (ref "J2") (pin "6") (pinfunction "VBUS_6") (pintype "passive"))
      (node (ref "J3") (pin "5") (pinfunction "VBUS_5") (pintype "passive"))
      (node (ref "J3") (pin "6") (pinfunction "VBUS_6") (pintype "passive"))
      (node (ref "J4") (pin "5") (pinfunction "VBUS_5") (pintype "passive"))
      (node (ref "J4") (pin "6") (pinfunction "VBUS_6") (pintype "passive"))
      (node (ref "J6") (pin "23") (pinfunction "23_23") (pintype "passive"))
      (node (ref "J6") (pin "24") (pinfunction "24_24") (pintype "passive"))
      (node (ref "J6") (pin "25") (pinfunction "25_25") (pintype "passive"))
      (node (ref "J6") (pin "26") (pinfunction "26_26") (pintype "passive"))
    )
    (net (code "35") (name "unconnected-(CF1-Pad9)") (class "Default")
      (node (ref "CF1") (pin "9") (pinfunction "9_9") (pintype "passive"))
    )
    (net (code "36") (name "unconnected-(CF1-Pad10)") (class "Default")
      (node (ref "CF1") (pin "10") (pinfunction "10_10") (pintype "passive"))
    )
    (net (code "37") (name "unconnected-(CF1-Pad11)") (class "Default")
      (node (ref "CF1") (pin "11") (pinfunction "11_11") (pintype "passive"))
    )
    (net (code "38") (name "unconnected-(CF1-Pad12)") (class "Default")
      (node (ref "CF1") (pin "12") (pinfunction "12_12") (pintype "passive"))
    )
    (net (code "39") (name "unconnected-(FIDUCIAL1-PadFIDUCIAL)") (class "Default")
      (node (ref "FIDUCIAL1") (pin "FIDUCIAL") (pinfunction "FIDUCIAL_FIDUCIAL") (pintype "no_connect"))
    )
    (net (code "40") (name "unconnected-(FIDUCIAL2-PadFIDUCIAL)") (class "Default")
      (node (ref "FIDUCIAL2") (pin "FIDUCIAL") (pinfunction "FIDUCIAL_FIDUCIAL") (pintype "no_connect"))
    )
    (net (code "41") (name "unconnected-(FIDUCIAL3-PadFIDUCIAL)") (class "Default")
      (node (ref "FIDUCIAL3") (pin "FIDUCIAL") (pinfunction "FIDUCIAL_FIDUCIAL") (pintype "no_connect"))
    )
    (net (code "42") (name "unconnected-(FIDUCIAL4-PadFIDUCIAL)") (class "Default")
      (node (ref "FIDUCIAL4") (pin "FIDUCIAL") (pinfunction "FIDUCIAL_FIDUCIAL") (pintype "no_connect"))
    )
    (net (code "43") (name "unconnected-(FIDUCIAL5-PadFIDUCIAL)") (class "Default")
      (node (ref "FIDUCIAL5") (pin "FIDUCIAL") (pinfunction "FIDUCIAL_FIDUCIAL") (pintype "no_connect"))
    )
    (net (code "44") (name "unconnected-(FIDUCIAL6-PadFIDUCIAL)") (class "Default")
      (node (ref "FIDUCIAL6") (pin "FIDUCIAL") (pinfunction "FIDUCIAL_FIDUCIAL") (pintype "no_connect"))
    )
    (net (code "45") (name "unconnected-(J6-Pad7)") (class "Default")
      (node (ref "J6") (pin "7") (pinfunction "7_7") (pintype "passive"))
    )
    (net (code "46") (name "unconnected-(J6-Pad8)") (class "Default")
      (node (ref "J6") (pin "8") (pinfunction "8_8") (pintype "passive"))
    )
    (net (code "47") (name "unconnected-(J6-Pad11)") (class "Default")
      (node (ref "J6") (pin "11") (pinfunction "11_11") (pintype "passive"))
    )
    (net (code "48") (name "unconnected-(J6-Pad12)") (class "Default")
      (node (ref "J6") (pin "12") (pinfunction "12_12") (pintype "passive"))
    )
    (net (code "49") (name "unconnected-(J6-Pad13)") (class "Default")
      (node (ref "J6") (pin "13") (pinfunction "13_13") (pintype "passive"))
    )
    (net (code "50") (name "unconnected-(J6-Pad14)") (class "Default")
      (node (ref "J6") (pin "14") (pinfunction "14_14") (pintype "passive"))
    )
    (net (code "51") (name "unconnected-(J6-Pad15)") (class "Default")
      (node (ref "J6") (pin "15") (pinfunction "15_15") (pintype "passive"))
    )
    (net (code "52") (name "unconnected-(J6-Pad16)") (class "Default")
      (node (ref "J6") (pin "16") (pinfunction "16_16") (pintype "passive"))
    )
    (net (code "53") (name "unconnected-(J6-Pad17)") (class "Default")
      (node (ref "J6") (pin "17") (pinfunction "17_17") (pintype "passive"))
    )
    (net (code "54") (name "unconnected-(J6-Pad18)") (class "Default")
      (node (ref "J6") (pin "18") (pinfunction "18_18") (pintype "passive"))
    )
    (net (code "55") (name "unconnected-(J6-Pad19)") (class "Default")
      (node (ref "J6") (pin "19") (pinfunction "19_19") (pintype "passive"))
    )
    (net (code "56") (name "unconnected-(J6-Pad20)") (class "Default")
      (node (ref "J6") (pin "20") (pinfunction "20_20") (pintype "passive"))
    )
    (net (code "57") (name "unconnected-(J6-Pad21)") (class "Default")
      (node (ref "J6") (pin "21") (pinfunction "21_21") (pintype "passive"))
    )
    (net (code "58") (name "unconnected-(J6-Pad22)") (class "Default")
      (node (ref "J6") (pin "22") (pinfunction "22_22") (pintype "passive"))
    )
    (net (code "59") (name "unconnected-(J6-Pad31)") (class "Default")
      (node (ref "J6") (pin "31") (pinfunction "31_31") (pintype "passive"))
    )
    (net (code "60") (name "unconnected-(J6-Pad32)") (class "Default")
      (node (ref "J6") (pin "32") (pinfunction "32_32") (pintype "passive"))
    )
    (net (code "61") (name "~{SD}") (class "Default")
      (node (ref "J1") (pin "1") (pinfunction "~{SD}_1") (pintype "passive"))
      (node (ref "J1") (pin "2") (pinfunction "~{SD}_2") (pintype "passive"))
      (node (ref "J2") (pin "1") (pinfunction "~{SD}_1") (pintype "passive"))
      (node (ref "J2") (pin "2") (pinfunction "~{SD}_2") (pintype "passive"))
      (node (ref "J3") (pin "1") (pinfunction "~{SD}_1") (pintype "passive"))
      (node (ref "J3") (pin "2") (pinfunction "~{SD}_2") (pintype "passive"))
      (node (ref "J4") (pin "1") (pinfunction "~{SD}_1") (pintype "passive"))
      (node (ref "J4") (pin "2") (pinfunction "~{SD}_2") (pintype "passive"))
      (node (ref "J6") (pin "39") (pinfunction "39_39") (pintype "passive"))
      (node (ref "J6") (pin "40") (pinfunction "40_40") (pintype "passive"))
    )
  )
)
